# KnobBox_v1.net
KiCad netlist of a schematic drawn in EAGLE
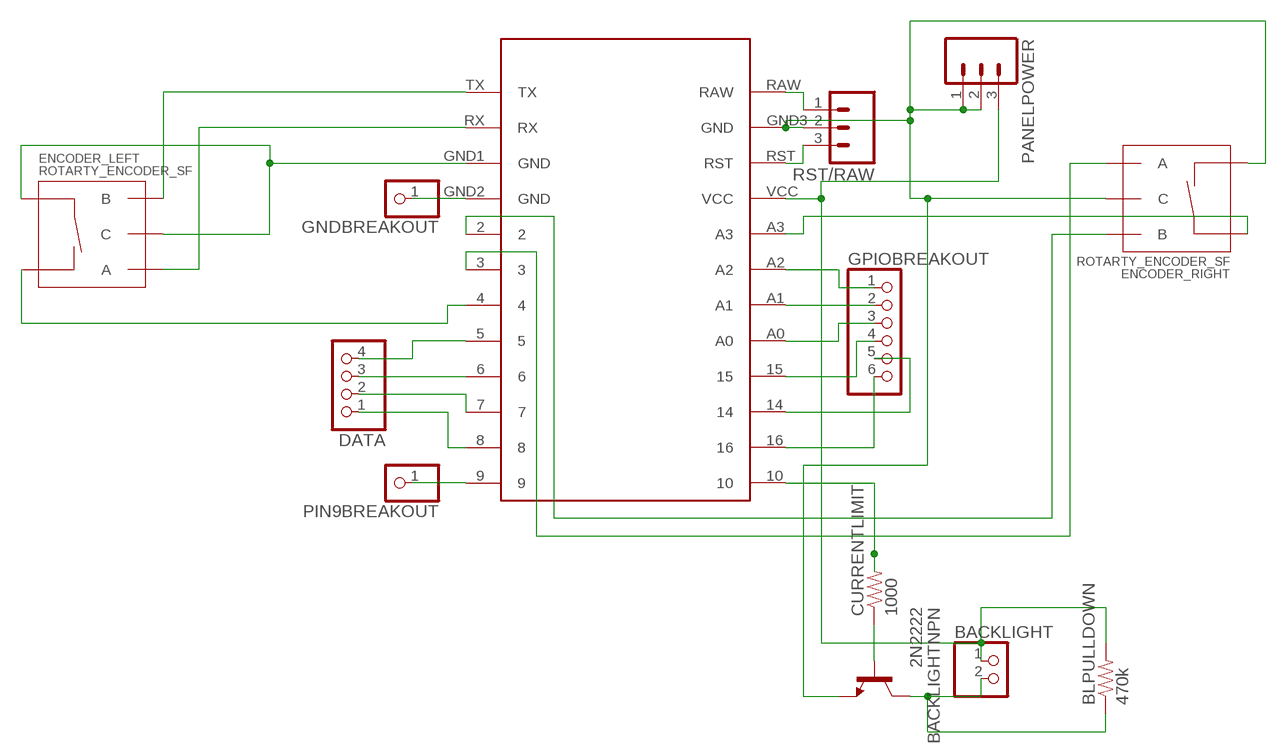
[diagram p0: schematic, sheet 1]

(export (version "E")
  (design (tool "Eeschema 10.0.6"))
  (components
    (comp (ref "BACKLIGHT")
      (value "PINHD-1X2")
      (footprint "eagle-import:1X02")
      (libsource (lib "eagle-import") (part "PINHD-1X2"))
    )
    (comp (ref "BACKLIGHTNPN")
      (value "2N2222")
      (footprint "eagle-import:TO92-EBC-OVAL")
      (libsource (lib "eagle-import") (part "2N2222"))
    )
    (comp (ref "BLPULLDOWN")
      (value "470k")
      (footprint "eagle-import:AXIAL-0.4")
      (libsource (lib "eagle-import") (part "RESISTORPTH-1/4W"))
    )
    (comp (ref "CURRENTLIMIT")
      (value "1000")
      (footprint "eagle-import:AXIAL-0.4")
      (libsource (lib "eagle-import") (part "RESISTORPTH-1/4W"))
    )
    (comp (ref "DATA")
      (value "PINHD-1X4")
      (footprint "eagle-import:1X04")
      (libsource (lib "eagle-import") (part "PINHD-1X4"))
    )
    (comp (ref "ENCODER_LEFT")
      (value "ROTARTY_ENCODER_SF")
      (footprint "eagle-import:ROTARY_ENC_SF_MOD")
      (libsource (lib "eagle-import") (part "ROTARTY_ENCODER_SF"))
    )
    (comp (ref "ENCODER_RIGHT")
      (value "ROTARTY_ENCODER_SF")
      (footprint "eagle-import:ROTARY_ENC_SF_MOD")
      (libsource (lib "eagle-import") (part "ROTARTY_ENCODER_SF"))
    )
    (comp (ref "GNDBREAKOUT")
      (value "PINHD-1X1BIG")
      (footprint "eagle-import:1X01_MOD")
      (libsource (lib "eagle-import") (part "PINHD-1X1BIG"))
    )
    (comp (ref "GPIOBREAKOUT")
      (value "PINHD-1X6")
      (footprint "eagle-import:1X06")
      (libsource (lib "eagle-import") (part "PINHD-1X6"))
    )
    (comp (ref "PANELPOWER")
      (value "M03PTH")
      (footprint "eagle-import:1X03")
      (libsource (lib "eagle-import") (part "M03PTH"))
    )
    (comp (ref "PIN9BREAKOUT")
      (value "PINHD-1X1BIG")
      (footprint "eagle-import:1X01_MOD")
      (libsource (lib "eagle-import") (part "PINHD-1X1BIG"))
    )
    (comp (ref "PROMICRO")
      (value "PROMICROROUND")
      (footprint "eagle-import:PROMICRO")
      (libsource (lib "eagle-import") (part "PROMICROROUND"))
    )
    (comp (ref "RST/RAW")
      (value "M03PTH")
      (footprint "eagle-import:1X03")
      (libsource (lib "eagle-import") (part "M03PTH"))
    )
  )
  (nets
    (net (code "1") (name "Net-(BACKLIGHTNPN-PadE)") (class "Default")
      (node (ref "BACKLIGHTNPN") (pin "E") (pinfunction "E_E") (pintype "passive"))
      (node (ref "ENCODER_RIGHT") (pin "C") (pinfunction "C_C") (pintype "bidirectional"))
      (node (ref "ENCODER_RIGHT") (pin "SW-") (pinfunction "SW-_SW-") (pintype "bidirectional"))
      (node (ref "PANELPOWER") (pin "1") (pinfunction "1_1") (pintype "passive"))
      (node (ref "PANELPOWER") (pin "2") (pinfunction "2_2") (pintype "passive"))
      (node (ref "PROMICRO") (pin "GND3") (pinfunction "GND_GND3") (pintype "bidirectional"))
      (node (ref "RST/RAW") (pin "2") (pinfunction "2_2") (pintype "passive"))
    )
    (net (code "2") (name "Net-(BLPULLDOWN-1)") (class "Default")
      (node (ref "BACKLIGHT") (pin "2") (pinfunction "2_2") (pintype "passive"))
      (node (ref "BACKLIGHTNPN") (pin "C") (pinfunction "C_C") (pintype "passive"))
      (node (ref "BLPULLDOWN") (pin "P$1") (pinfunction "1_P$1") (pintype "passive"))
    )
    (net (code "3") (name "Net-(BLPULLDOWN-2)") (class "Default")
      (node (ref "BACKLIGHT") (pin "1") (pinfunction "1_1") (pintype "passive"))
      (node (ref "BLPULLDOWN") (pin "P$2") (pinfunction "2_P$2") (pintype "passive"))
      (node (ref "PANELPOWER") (pin "3") (pinfunction "3_3") (pintype "passive"))
      (node (ref "PROMICRO") (pin "VCC") (pinfunction "VCC_VCC") (pintype "bidirectional"))
    )
    (net (code "4") (name "Net-(CURRENTLIMIT-1)") (class "Default")
      (node (ref "BACKLIGHTNPN") (pin "B") (pinfunction "B_B") (pintype "passive"))
      (node (ref "CURRENTLIMIT") (pin "P$1") (pinfunction "1_P$1") (pintype "passive"))
    )
    (net (code "5") (name "Net-(CURRENTLIMIT-2)") (class "Default")
      (node (ref "CURRENTLIMIT") (pin "P$2") (pinfunction "2_P$2") (pintype "passive"))
      (node (ref "PROMICRO") (pin "10") (pinfunction "10_10") (pintype "bidirectional"))
    )
    (net (code "6") (name "Net-(DATA-Pad1)") (class "Default")
      (node (ref "DATA") (pin "1") (pinfunction "1_1") (pintype "passive"))
      (node (ref "PROMICRO") (pin "8") (pinfunction "8_8") (pintype "bidirectional"))
    )
    (net (code "7") (name "Net-(DATA-Pad2)") (class "Default")
      (node (ref "DATA") (pin "2") (pinfunction "2_2") (pintype "passive"))
      (node (ref "PROMICRO") (pin "7") (pinfunction "7_7") (pintype "bidirectional"))
    )
    (net (code "8") (name "Net-(DATA-Pad3)") (class "Default")
      (node (ref "DATA") (pin "3") (pinfunction "3_3") (pintype "passive"))
      (node (ref "PROMICRO") (pin "6") (pinfunction "6_6") (pintype "bidirectional"))
    )
    (net (code "9") (name "Net-(DATA-Pad4)") (class "Default")
      (node (ref "DATA") (pin "4") (pinfunction "4_4") (pintype "passive"))
      (node (ref "PROMICRO") (pin "5") (pinfunction "5_5") (pintype "bidirectional"))
    )
    (net (code "10") (name "Net-(ENCODER_LEFT-PadA)") (class "Default")
      (node (ref "ENCODER_LEFT") (pin "A") (pinfunction "A_A") (pintype "bidirectional"))
      (node (ref "PROMICRO") (pin "RX") (pinfunction "RX_RX") (pintype "bidirectional"))
    )
    (net (code "11") (name "Net-(ENCODER_LEFT-PadB)") (class "Default")
      (node (ref "ENCODER_LEFT") (pin "B") (pinfunction "B_B") (pintype "bidirectional"))
      (node (ref "PROMICRO") (pin "TX") (pinfunction "TX_TX") (pintype "bidirectional"))
    )
    (net (code "12") (name "Net-(ENCODER_LEFT-PadC)") (class "Default")
      (node (ref "ENCODER_LEFT") (pin "C") (pinfunction "C_C") (pintype "bidirectional"))
      (node (ref "ENCODER_LEFT") (pin "SW+") (pinfunction "SW+_SW+") (pintype "bidirectional"))
      (node (ref "PROMICRO") (pin "GND1") (pinfunction "GND_GND1") (pintype "bidirectional"))
    )
    (net (code "13") (name "Net-(ENCODER_LEFT-PadSW-)") (class "Default")
      (node (ref "ENCODER_LEFT") (pin "SW-") (pinfunction "SW-_SW-") (pintype "bidirectional"))
      (node (ref "PROMICRO") (pin "4") (pinfunction "4_4") (pintype "bidirectional"))
    )
    (net (code "14") (name "Net-(ENCODER_RIGHT-PadA)") (class "Default")
      (node (ref "ENCODER_RIGHT") (pin "A") (pinfunction "A_A") (pintype "bidirectional"))
      (node (ref "PROMICRO") (pin "3") (pinfunction "3_3") (pintype "bidirectional"))
    )
    (net (code "15") (name "Net-(ENCODER_RIGHT-PadB)") (class "Default")
      (node (ref "ENCODER_RIGHT") (pin "B") (pinfunction "B_B") (pintype "bidirectional"))
      (node (ref "PROMICRO") (pin "2") (pinfunction "2_2") (pintype "bidirectional"))
    )
    (net (code "16") (name "Net-(ENCODER_RIGHT-PadSW+)") (class "Default")
      (node (ref "ENCODER_RIGHT") (pin "SW+") (pinfunction "SW+_SW+") (pintype "bidirectional"))
      (node (ref "PROMICRO") (pin "A3") (pinfunction "A3_A3") (pintype "bidirectional"))
    )
    (net (code "17") (name "Net-(GNDBREAKOUT-Pad1)") (class "Default")
      (node (ref "GNDBREAKOUT") (pin "1") (pinfunction "1_1") (pintype "passive"))
      (node (ref "PROMICRO") (pin "GND2") (pinfunction "GND_GND2") (pintype "bidirectional"))
    )
    (net (code "18") (name "Net-(GPIOBREAKOUT-Pad1)") (class "Default")
      (node (ref "GPIOBREAKOUT") (pin "1") (pinfunction "1_1") (pintype "passive"))
      (node (ref "PROMICRO") (pin "A2") (pinfunction "A2_A2") (pintype "bidirectional"))
    )
    (net (code "19") (name "Net-(GPIOBREAKOUT-Pad2)") (class "Default")
      (node (ref "GPIOBREAKOUT") (pin "2") (pinfunction "2_2") (pintype "passive"))
      (node (ref "PROMICRO") (pin "A1") (pinfunction "A1_A1") (pintype "bidirectional"))
    )
    (net (code "20") (name "Net-(GPIOBREAKOUT-Pad3)") (class "Default")
      (node (ref "GPIOBREAKOUT") (pin "3") (pinfunction "3_3") (pintype "passive"))
      (node (ref "PROMICRO") (pin "A0") (pinfunction "A0_A0") (pintype "bidirectional"))
    )
    (net (code "21") (name "Net-(GPIOBREAKOUT-Pad4)") (class "Default")
      (node (ref "GPIOBREAKOUT") (pin "4") (pinfunction "4_4") (pintype "passive"))
      (node (ref "PROMICRO") (pin "15") (pinfunction "15_15") (pintype "bidirectional"))
    )
    (net (code "22") (name "Net-(GPIOBREAKOUT-Pad5)") (class "Default")
      (node (ref "GPIOBREAKOUT") (pin "5") (pinfunction "5_5") (pintype "passive"))
      (node (ref "PROMICRO") (pin "14") (pinfunction "14_14") (pintype "bidirectional"))
    )
    (net (code "23") (name "Net-(GPIOBREAKOUT-Pad6)") (class "Default")
      (node (ref "GPIOBREAKOUT") (pin "6") (pinfunction "6_6") (pintype "passive"))
      (node (ref "PROMICRO") (pin "16") (pinfunction "16_16") (pintype "bidirectional"))
    )
    (net (code "24") (name "Net-(PIN9BREAKOUT-Pad1)") (class "Default")
      (node (ref "PIN9BREAKOUT") (pin "1") (pinfunction "1_1") (pintype "passive"))
      (node (ref "PROMICRO") (pin "9") (pinfunction "9_9") (pintype "bidirectional"))
    )
    (net (code "25") (name "Net-(PROMICRO-PadRAW)") (class "Default")
      (node (ref "PROMICRO") (pin "RAW") (pinfunction "RAW_RAW") (pintype "bidirectional"))
      (node (ref "RST/RAW") (pin "1") (pinfunction "1_1") (pintype "passive"))
    )
    (net (code "26") (name "Net-(PROMICRO-PadRST)") (class "Default")
      (node (ref "PROMICRO") (pin "RST") (pinfunction "RST_RST") (pintype "bidirectional"))
      (node (ref "RST/RAW") (pin "3") (pinfunction "3_3") (pintype "passive"))
    )
  )
)
